# ARE_adaptadora_dsPIC-PIC32_64pin.net
KiCad netlist of a schematic drawn in EAGLE
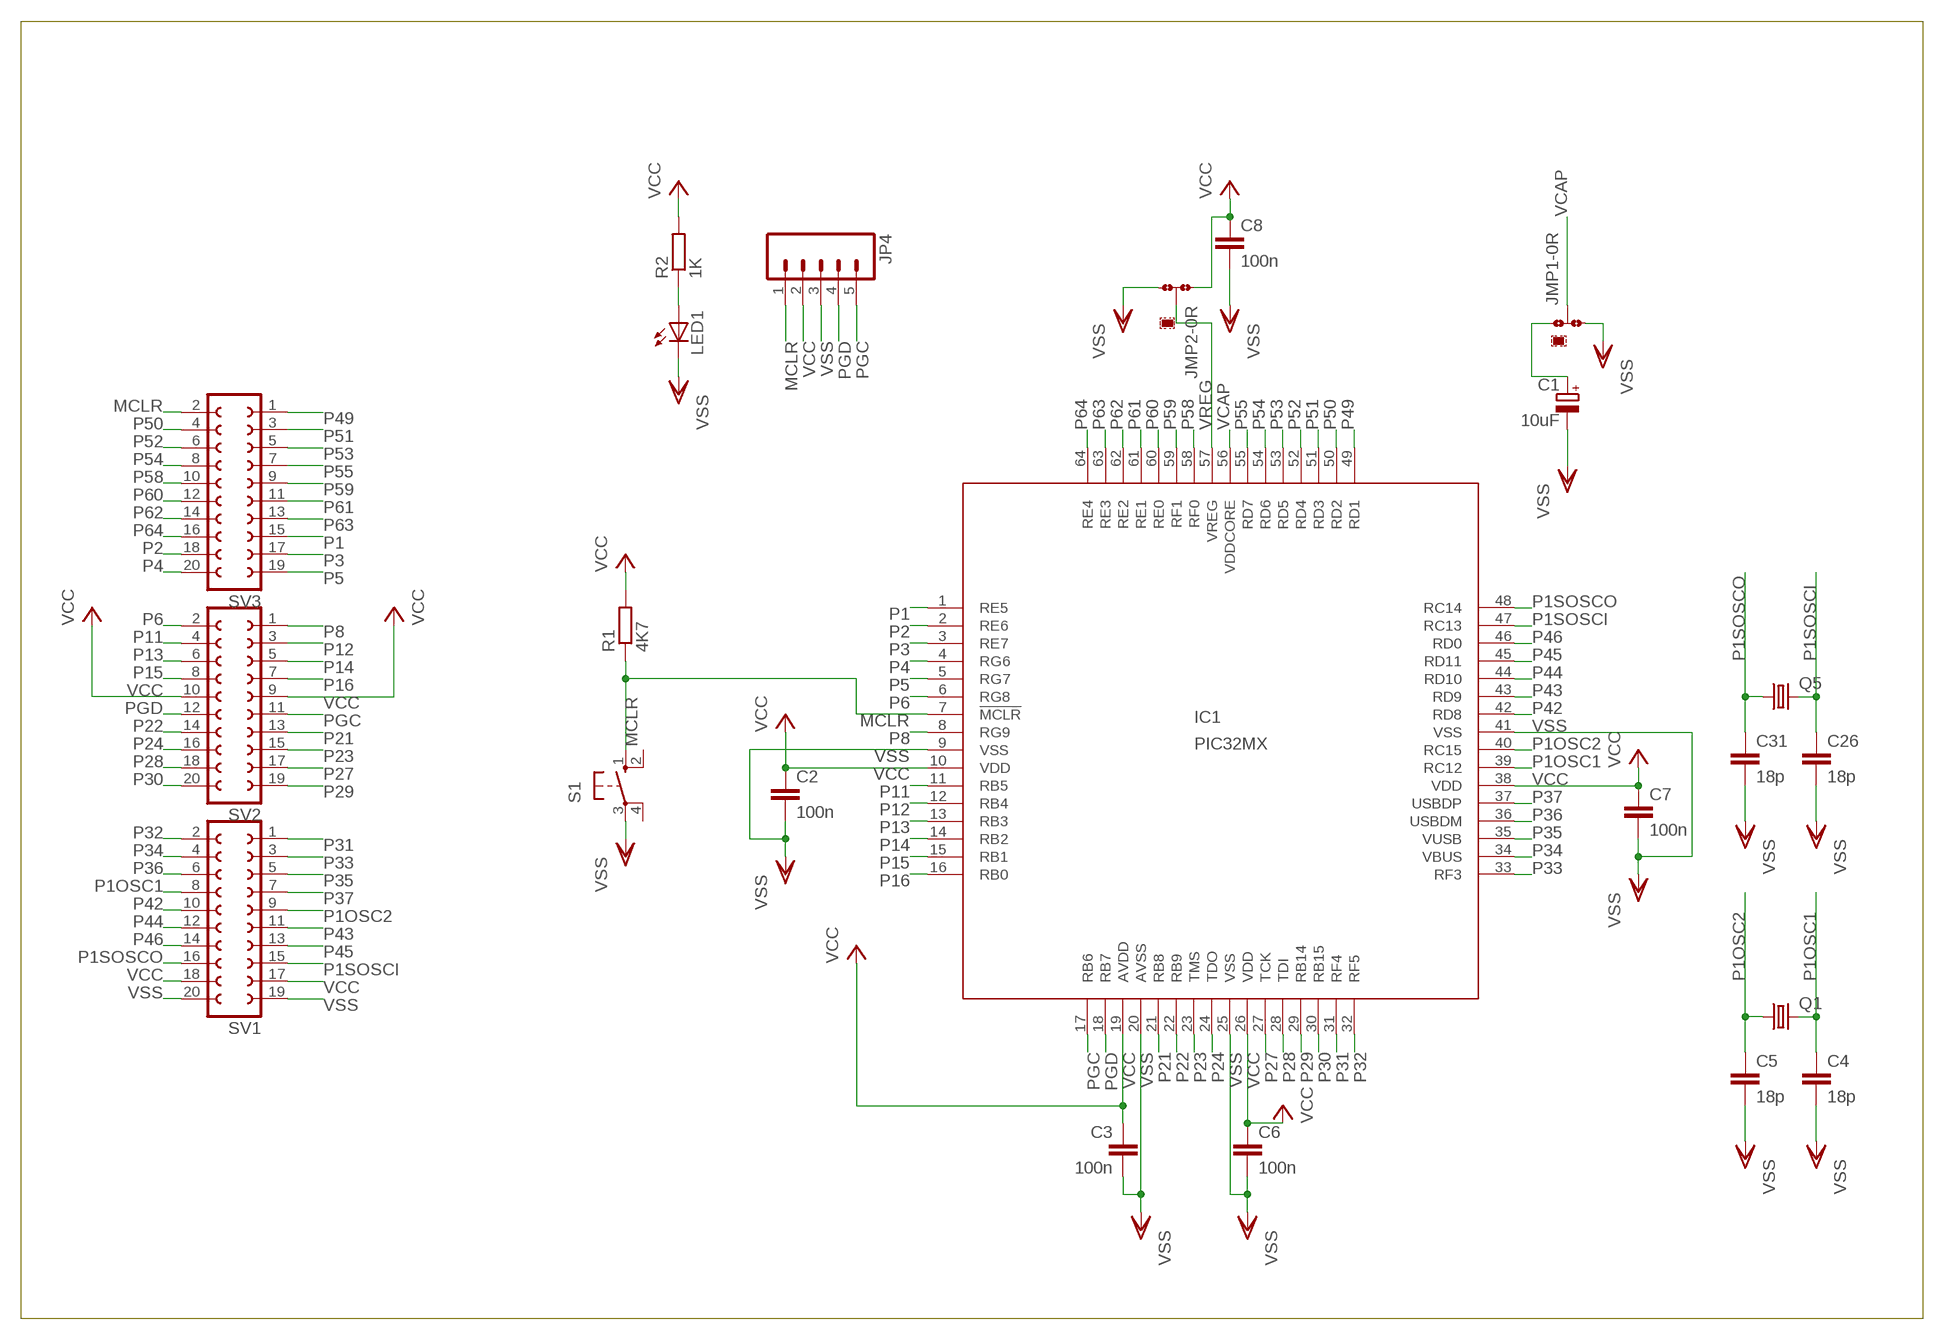
[diagram p0: schematic, sheet 1]

(export (version "E")
  (design (tool "Eeschema 10.0.6"))
  (components
    (comp (ref "C1")
      (value "10uF")
      (footprint "eagle-import:SMC_C")
      (libsource (lib "eagle-import") (part "CPOL-EUSMCC"))
    )
    (comp (ref "C2")
      (value "100n")
      (footprint "eagle-import:C0805")
      (libsource (lib "eagle-import") (part "C-EUC0805"))
    )
    (comp (ref "C3")
      (value "100n")
      (footprint "eagle-import:C0805")
      (libsource (lib "eagle-import") (part "C-EUC0805"))
    )
    (comp (ref "C4")
      (value "18p")
      (footprint "eagle-import:C0805")
      (libsource (lib "eagle-import") (part "C-EUC0805"))
    )
    (comp (ref "C5")
      (value "18p")
      (footprint "eagle-import:C0805")
      (libsource (lib "eagle-import") (part "C-EUC0805"))
    )
    (comp (ref "C6")
      (value "100n")
      (footprint "eagle-import:C0805")
      (libsource (lib "eagle-import") (part "C-EUC0805"))
    )
    (comp (ref "C7")
      (value "100n")
      (footprint "eagle-import:C0805")
      (libsource (lib "eagle-import") (part "C-EUC0805"))
    )
    (comp (ref "C8")
      (value "100n")
      (footprint "eagle-import:C0805")
      (libsource (lib "eagle-import") (part "C-EUC0805"))
    )
    (comp (ref "C26")
      (value "18p")
      (footprint "eagle-import:C0805")
      (libsource (lib "eagle-import") (part "C-EUC0805"))
    )
    (comp (ref "C31")
      (value "18p")
      (footprint "eagle-import:C0805")
      (libsource (lib "eagle-import") (part "C-EUC0805"))
    )
    (comp (ref "IC1")
      (value "PIC32MX")
      (footprint "eagle-import:TQFP64-10X10")
      (libsource (lib "eagle-import") (part "PIC32MX440F256H"))
    )
    (comp (ref "JMP1")
      (value "0R-JUMPA")
      (footprint "eagle-import:A0R-JMP")
      (libsource (lib "eagle-import") (part "0R-JUMPA"))
    )
    (comp (ref "JMP2")
      (value "0R-JUMPA")
      (footprint "eagle-import:A0R-JMP")
      (libsource (lib "eagle-import") (part "0R-JUMPA"))
    )
    (comp (ref "JP4")
      (value "M05PTH")
      (footprint "eagle-import:1X05")
      (libsource (lib "eagle-import") (part "M05PTH"))
    )
    (comp (ref "LED1")
      (value "LEDCHIPLED_0805")
      (footprint "eagle-import:CHIPLED_0805")
      (libsource (lib "eagle-import") (part "LEDCHIPLED_0805"))
    )
    (comp (ref "Q1")
      (value "CRYSTALHC18U-V")
      (footprint "eagle-import:HC18U-V")
      (libsource (lib "eagle-import") (part "CRYSTALHC18U-V"))
    )
    (comp (ref "Q5")
      (value "CRYSTALHC18U-V")
      (footprint "eagle-import:HC18U-V")
      (libsource (lib "eagle-import") (part "CRYSTALHC18U-V"))
    )
    (comp (ref "R1")
      (value "4K7")
      (footprint "eagle-import:R0805")
      (libsource (lib "eagle-import") (part "R-EU_R0805"))
    )
    (comp (ref "R2")
      (value "1K")
      (footprint "eagle-import:R0805")
      (libsource (lib "eagle-import") (part "R-EU_R0805"))
    )
    (comp (ref "S1")
      (value "10-XX")
      (footprint "eagle-import:B3F-10XX")
      (fields
        (field (name "MPN") "B3F-1000")
        (field (name "MPN_1") "B3F-1000")
        (field (name "OC_FARNELL") "176432")
        (field (name "OC_NEWARK") "36M3542")
      )
      (libsource (lib "eagle-import") (part "10-XX"))
    )
    (comp (ref "SV1")
      (value "FE10-2W")
      (footprint "eagle-import:FE10-2W")
      (libsource (lib "eagle-import") (part "FE10-2W"))
    )
    (comp (ref "SV2")
      (value "FE10-2W")
      (footprint "eagle-import:FE10-2W")
      (libsource (lib "eagle-import") (part "FE10-2W"))
    )
    (comp (ref "SV3")
      (value "FE10-2W")
      (footprint "eagle-import:FE10-2W")
      (libsource (lib "eagle-import") (part "FE10-2W"))
    )
  )
  (nets
    (net (code "1") (name "/MCLR") (class "Default")
      (node (ref "IC1") (pin "7") (pinfunction "~{MCLR}_7") (pintype "input"))
      (node (ref "JP4") (pin "1") (pinfunction "1_1") (pintype "passive"))
      (node (ref "R1") (pin "1") (pinfunction "1_1") (pintype "passive"))
      (node (ref "S1") (pin "1") (pinfunction "S_1") (pintype "passive"))
      (node (ref "SV3") (pin "2") (pinfunction "2_2") (pintype "passive"))
    )
    (net (code "2") (name "/P1") (class "Default")
      (node (ref "IC1") (pin "1") (pinfunction "RE5_1") (pintype "bidirectional"))
      (node (ref "SV3") (pin "15") (pinfunction "15_15") (pintype "passive"))
    )
    (net (code "3") (name "/P1OSC1") (class "Default")
      (node (ref "C4") (pin "1") (pinfunction "1_1") (pintype "passive"))
      (node (ref "IC1") (pin "39") (pinfunction "RC12_39") (pintype "bidirectional"))
      (node (ref "Q1") (pin "2") (pinfunction "2_2") (pintype "passive"))
      (node (ref "SV1") (pin "8") (pinfunction "8_8") (pintype "passive"))
    )
    (net (code "4") (name "/P1OSC2") (class "Default")
      (node (ref "C5") (pin "1") (pinfunction "1_1") (pintype "passive"))
      (node (ref "IC1") (pin "40") (pinfunction "RC15_40") (pintype "bidirectional"))
      (node (ref "Q1") (pin "1") (pinfunction "1_1") (pintype "passive"))
      (node (ref "SV1") (pin "9") (pinfunction "9_9") (pintype "passive"))
    )
    (net (code "5") (name "/P1SOSCI") (class "Default")
      (node (ref "C26") (pin "1") (pinfunction "1_1") (pintype "passive"))
      (node (ref "IC1") (pin "47") (pinfunction "RC13_47") (pintype "bidirectional"))
      (node (ref "Q5") (pin "2") (pinfunction "2_2") (pintype "passive"))
      (node (ref "SV1") (pin "15") (pinfunction "15_15") (pintype "passive"))
    )
    (net (code "6") (name "/P1SOSCO") (class "Default")
      (node (ref "C31") (pin "1") (pinfunction "1_1") (pintype "passive"))
      (node (ref "IC1") (pin "48") (pinfunction "RC14_48") (pintype "bidirectional"))
      (node (ref "Q5") (pin "1") (pinfunction "1_1") (pintype "passive"))
      (node (ref "SV1") (pin "16") (pinfunction "16_16") (pintype "passive"))
    )
    (net (code "7") (name "/P2") (class "Default")
      (node (ref "IC1") (pin "2") (pinfunction "RE6_2") (pintype "bidirectional"))
      (node (ref "SV3") (pin "18") (pinfunction "18_18") (pintype "passive"))
    )
    (net (code "8") (name "/P3") (class "Default")
      (node (ref "IC1") (pin "3") (pinfunction "RE7_3") (pintype "bidirectional"))
      (node (ref "SV3") (pin "17") (pinfunction "17_17") (pintype "passive"))
    )
    (net (code "9") (name "/P4") (class "Default")
      (node (ref "IC1") (pin "4") (pinfunction "RG6_4") (pintype "bidirectional"))
      (node (ref "SV3") (pin "20") (pinfunction "20_20") (pintype "passive"))
    )
    (net (code "10") (name "/P5") (class "Default")
      (node (ref "IC1") (pin "5") (pinfunction "RG7_5") (pintype "bidirectional"))
      (node (ref "SV3") (pin "19") (pinfunction "19_19") (pintype "passive"))
    )
    (net (code "11") (name "/P6") (class "Default")
      (node (ref "IC1") (pin "6") (pinfunction "RG8_6") (pintype "bidirectional"))
      (node (ref "SV2") (pin "2") (pinfunction "2_2") (pintype "passive"))
    )
    (net (code "12") (name "/P8") (class "Default")
      (node (ref "IC1") (pin "8") (pinfunction "RG9_8") (pintype "bidirectional"))
      (node (ref "SV2") (pin "1") (pinfunction "1_1") (pintype "passive"))
    )
    (net (code "13") (name "/P11") (class "Default")
      (node (ref "IC1") (pin "11") (pinfunction "RB5_11") (pintype "bidirectional"))
      (node (ref "SV2") (pin "4") (pinfunction "4_4") (pintype "passive"))
    )
    (net (code "14") (name "/P12") (class "Default")
      (node (ref "IC1") (pin "12") (pinfunction "RB4_12") (pintype "bidirectional"))
      (node (ref "SV2") (pin "3") (pinfunction "3_3") (pintype "passive"))
    )
    (net (code "15") (name "/P13") (class "Default")
      (node (ref "IC1") (pin "13") (pinfunction "RB3_13") (pintype "bidirectional"))
      (node (ref "SV2") (pin "6") (pinfunction "6_6") (pintype "passive"))
    )
    (net (code "16") (name "/P14") (class "Default")
      (node (ref "IC1") (pin "14") (pinfunction "RB2_14") (pintype "bidirectional"))
      (node (ref "SV2") (pin "5") (pinfunction "5_5") (pintype "passive"))
    )
    (net (code "17") (name "/P15") (class "Default")
      (node (ref "IC1") (pin "15") (pinfunction "RB1_15") (pintype "bidirectional"))
      (node (ref "SV2") (pin "8") (pinfunction "8_8") (pintype "passive"))
    )
    (net (code "18") (name "/P16") (class "Default")
      (node (ref "IC1") (pin "16") (pinfunction "RB0_16") (pintype "bidirectional"))
      (node (ref "SV2") (pin "7") (pinfunction "7_7") (pintype "passive"))
    )
    (net (code "19") (name "/P21") (class "Default")
      (node (ref "IC1") (pin "21") (pinfunction "RB8_21") (pintype "bidirectional"))
      (node (ref "SV2") (pin "13") (pinfunction "13_13") (pintype "passive"))
    )
    (net (code "20") (name "/P22") (class "Default")
      (node (ref "IC1") (pin "22") (pinfunction "RB9_22") (pintype "bidirectional"))
      (node (ref "SV2") (pin "14") (pinfunction "14_14") (pintype "passive"))
    )
    (net (code "21") (name "/P23") (class "Default")
      (node (ref "IC1") (pin "23") (pinfunction "TMS_23") (pintype "input"))
      (node (ref "SV2") (pin "15") (pinfunction "15_15") (pintype "passive"))
    )
    (net (code "22") (name "/P24") (class "Default")
      (node (ref "IC1") (pin "24") (pinfunction "TDO_24") (pintype "output"))
      (node (ref "SV2") (pin "16") (pinfunction "16_16") (pintype "passive"))
    )
    (net (code "23") (name "/P27") (class "Default")
      (node (ref "IC1") (pin "27") (pinfunction "TCK_27") (pintype "input"))
      (node (ref "SV2") (pin "17") (pinfunction "17_17") (pintype "passive"))
    )
    (net (code "24") (name "/P28") (class "Default")
      (node (ref "IC1") (pin "28") (pinfunction "TDI_28") (pintype "input"))
      (node (ref "SV2") (pin "18") (pinfunction "18_18") (pintype "passive"))
    )
    (net (code "25") (name "/P29") (class "Default")
      (node (ref "IC1") (pin "29") (pinfunction "RB14_29") (pintype "bidirectional"))
      (node (ref "SV2") (pin "19") (pinfunction "19_19") (pintype "passive"))
    )
    (net (code "26") (name "/P30") (class "Default")
      (node (ref "IC1") (pin "30") (pinfunction "RB15_30") (pintype "bidirectional"))
      (node (ref "SV2") (pin "20") (pinfunction "20_20") (pintype "passive"))
    )
    (net (code "27") (name "/P31") (class "Default")
      (node (ref "IC1") (pin "31") (pinfunction "RF4_31") (pintype "bidirectional"))
      (node (ref "SV1") (pin "1") (pinfunction "1_1") (pintype "passive"))
    )
    (net (code "28") (name "/P32") (class "Default")
      (node (ref "IC1") (pin "32") (pinfunction "RF5_32") (pintype "bidirectional"))
      (node (ref "SV1") (pin "2") (pinfunction "2_2") (pintype "passive"))
    )
    (net (code "29") (name "/P33") (class "Default")
      (node (ref "IC1") (pin "33") (pinfunction "RF3_33") (pintype "bidirectional"))
      (node (ref "SV1") (pin "3") (pinfunction "3_3") (pintype "passive"))
    )
    (net (code "30") (name "/P34") (class "Default")
      (node (ref "IC1") (pin "34") (pinfunction "VBUS_34") (pintype "bidirectional"))
      (node (ref "SV1") (pin "4") (pinfunction "4_4") (pintype "passive"))
    )
    (net (code "31") (name "/P35") (class "Default")
      (node (ref "IC1") (pin "35") (pinfunction "VUSB_35") (pintype "passive"))
      (node (ref "SV1") (pin "5") (pinfunction "5_5") (pintype "passive"))
    )
    (net (code "32") (name "/P36") (class "Default")
      (node (ref "IC1") (pin "36") (pinfunction "USBDM_36") (pintype "bidirectional"))
      (node (ref "SV1") (pin "6") (pinfunction "6_6") (pintype "passive"))
    )
    (net (code "33") (name "/P37") (class "Default")
      (node (ref "IC1") (pin "37") (pinfunction "USBDP_37") (pintype "bidirectional"))
      (node (ref "SV1") (pin "7") (pinfunction "7_7") (pintype "passive"))
    )
    (net (code "34") (name "/P42") (class "Default")
      (node (ref "IC1") (pin "42") (pinfunction "RD8_42") (pintype "bidirectional"))
      (node (ref "SV1") (pin "10") (pinfunction "10_10") (pintype "passive"))
    )
    (net (code "35") (name "/P43") (class "Default")
      (node (ref "IC1") (pin "43") (pinfunction "RD9_43") (pintype "bidirectional"))
      (node (ref "SV1") (pin "11") (pinfunction "11_11") (pintype "passive"))
    )
    (net (code "36") (name "/P44") (class "Default")
      (node (ref "IC1") (pin "44") (pinfunction "RD10_44") (pintype "bidirectional"))
      (node (ref "SV1") (pin "12") (pinfunction "12_12") (pintype "passive"))
    )
    (net (code "37") (name "/P45") (class "Default")
      (node (ref "IC1") (pin "45") (pinfunction "RD11_45") (pintype "bidirectional"))
      (node (ref "SV1") (pin "13") (pinfunction "13_13") (pintype "passive"))
    )
    (net (code "38") (name "/P46") (class "Default")
      (node (ref "IC1") (pin "46") (pinfunction "RD0_46") (pintype "bidirectional"))
      (node (ref "SV1") (pin "14") (pinfunction "14_14") (pintype "passive"))
    )
    (net (code "39") (name "/P49") (class "Default")
      (node (ref "IC1") (pin "49") (pinfunction "RD1_49") (pintype "bidirectional"))
      (node (ref "SV3") (pin "1") (pinfunction "1_1") (pintype "passive"))
    )
    (net (code "40") (name "/P50") (class "Default")
      (node (ref "IC1") (pin "50") (pinfunction "RD2_50") (pintype "bidirectional"))
      (node (ref "SV3") (pin "4") (pinfunction "4_4") (pintype "passive"))
    )
    (net (code "41") (name "/P51") (class "Default")
      (node (ref "IC1") (pin "51") (pinfunction "RD3_51") (pintype "bidirectional"))
      (node (ref "SV3") (pin "3") (pinfunction "3_3") (pintype "passive"))
    )
    (net (code "42") (name "/P52") (class "Default")
      (node (ref "IC1") (pin "52") (pinfunction "RD4_52") (pintype "bidirectional"))
      (node (ref "SV3") (pin "6") (pinfunction "6_6") (pintype "passive"))
    )
    (net (code "43") (name "/P53") (class "Default")
      (node (ref "IC1") (pin "53") (pinfunction "RD5_53") (pintype "bidirectional"))
      (node (ref "SV3") (pin "5") (pinfunction "5_5") (pintype "passive"))
    )
    (net (code "44") (name "/P54") (class "Default")
      (node (ref "IC1") (pin "54") (pinfunction "RD6_54") (pintype "bidirectional"))
      (node (ref "SV3") (pin "8") (pinfunction "8_8") (pintype "passive"))
    )
    (net (code "45") (name "/P55") (class "Default")
      (node (ref "IC1") (pin "55") (pinfunction "RD7_55") (pintype "bidirectional"))
      (node (ref "SV3") (pin "7") (pinfunction "7_7") (pintype "passive"))
    )
    (net (code "46") (name "/P58") (class "Default")
      (node (ref "IC1") (pin "58") (pinfunction "RF0_58") (pintype "bidirectional"))
      (node (ref "SV3") (pin "10") (pinfunction "10_10") (pintype "passive"))
    )
    (net (code "47") (name "/P59") (class "Default")
      (node (ref "IC1") (pin "59") (pinfunction "RF1_59") (pintype "bidirectional"))
      (node (ref "SV3") (pin "9") (pinfunction "9_9") (pintype "passive"))
    )
    (net (code "48") (name "/P60") (class "Default")
      (node (ref "IC1") (pin "60") (pinfunction "RE0_60") (pintype "bidirectional"))
      (node (ref "SV3") (pin "12") (pinfunction "12_12") (pintype "passive"))
    )
    (net (code "49") (name "/P61") (class "Default")
      (node (ref "IC1") (pin "61") (pinfunction "RE1_61") (pintype "bidirectional"))
      (node (ref "SV3") (pin "11") (pinfunction "11_11") (pintype "passive"))
    )
    (net (code "50") (name "/P62") (class "Default")
      (node (ref "IC1") (pin "62") (pinfunction "RE2_62") (pintype "bidirectional"))
      (node (ref "SV3") (pin "14") (pinfunction "14_14") (pintype "passive"))
    )
    (net (code "51") (name "/P63") (class "Default")
      (node (ref "IC1") (pin "63") (pinfunction "RE3_63") (pintype "bidirectional"))
      (node (ref "SV3") (pin "13") (pinfunction "13_13") (pintype "passive"))
    )
    (net (code "52") (name "/P64") (class "Default")
      (node (ref "IC1") (pin "64") (pinfunction "RE4_64") (pintype "bidirectional"))
      (node (ref "SV3") (pin "16") (pinfunction "16_16") (pintype "passive"))
    )
    (net (code "53") (name "/PGC") (class "Default")
      (node (ref "IC1") (pin "17") (pinfunction "RB6_17") (pintype "bidirectional"))
      (node (ref "JP4") (pin "5") (pinfunction "5_5") (pintype "passive"))
      (node (ref "SV2") (pin "11") (pinfunction "11_11") (pintype "passive"))
    )
    (net (code "54") (name "/PGD") (class "Default")
      (node (ref "IC1") (pin "18") (pinfunction "RB7_18") (pintype "bidirectional"))
      (node (ref "JP4") (pin "4") (pinfunction "4_4") (pintype "passive"))
      (node (ref "SV2") (pin "12") (pinfunction "12_12") (pintype "passive"))
    )
    (net (code "55") (name "/VCAP") (class "Default")
      (node (ref "IC1") (pin "56") (pinfunction "VDDCORE_56") (pintype "power_in"))
      (node (ref "JMP1") (pin "2") (pinfunction "2_2") (pintype "passive"))
    )
    (net (code "56") (name "/VREG") (class "Default")
      (node (ref "IC1") (pin "57") (pinfunction "VREG_57") (pintype "passive"))
      (node (ref "JMP2") (pin "2") (pinfunction "2_2") (pintype "passive"))
    )
    (net (code "57") (name "Net-(C1-Pad+)") (class "Default")
      (node (ref "C1") (pin "+") (pinfunction "+_+") (pintype "passive"))
      (node (ref "JMP1") (pin "1") (pinfunction "1_1") (pintype "passive"))
    )
    (net (code "58") (name "Net-(LED1-PadA)") (class "Default")
      (node (ref "LED1") (pin "A") (pinfunction "A_A") (pintype "passive"))
      (node (ref "R2") (pin "1") (pinfunction "1_1") (pintype "passive"))
    )
    (net (code "59") (name "VCC") (class "Default")
      (node (ref "C2") (pin "1") (pinfunction "1_1") (pintype "passive"))
      (node (ref "C3") (pin "1") (pinfunction "1_1") (pintype "passive"))
      (node (ref "C6") (pin "1") (pinfunction "1_1") (pintype "passive"))
      (node (ref "C7") (pin "1") (pinfunction "1_1") (pintype "passive"))
      (node (ref "C8") (pin "1") (pinfunction "1_1") (pintype "passive"))
      (node (ref "IC1") (pin "10") (pinfunction "VDD_10") (pintype "power_in"))
      (node (ref "IC1") (pin "19") (pinfunction "AVDD_19") (pintype "power_in"))
      (node (ref "IC1") (pin "26") (pinfunction "VDD_26") (pintype "power_in"))
      (node (ref "IC1") (pin "38") (pinfunction "VDD_38") (pintype "power_in"))
      (node (ref "JMP2") (pin "1") (pinfunction "1_1") (pintype "passive"))
      (node (ref "JP4") (pin "2") (pinfunction "2_2") (pintype "passive"))
      (node (ref "R1") (pin "2") (pinfunction "2_2") (pintype "passive"))
      (node (ref "R2") (pin "2") (pinfunction "2_2") (pintype "passive"))
      (node (ref "SV1") (pin "17") (pinfunction "17_17") (pintype "passive"))
      (node (ref "SV1") (pin "18") (pinfunction "18_18") (pintype "passive"))
      (node (ref "SV2") (pin "10") (pinfunction "10_10") (pintype "passive"))
      (node (ref "SV2") (pin "9") (pinfunction "9_9") (pintype "passive"))
    )
    (net (code "60") (name "VSS") (class "Default")
      (node (ref "C1") (pin "-") (pinfunction "-_-") (pintype "passive"))
      (node (ref "C2") (pin "2") (pinfunction "2_2") (pintype "passive"))
      (node (ref "C26") (pin "2") (pinfunction "2_2") (pintype "passive"))
      (node (ref "C3") (pin "2") (pinfunction "2_2") (pintype "passive"))
      (node (ref "C31") (pin "2") (pinfunction "2_2") (pintype "passive"))
      (node (ref "C4") (pin "2") (pinfunction "2_2") (pintype "passive"))
      (node (ref "C5") (pin "2") (pinfunction "2_2") (pintype "passive"))
      (node (ref "C6") (pin "2") (pinfunction "2_2") (pintype "passive"))
      (node (ref "C7") (pin "2") (pinfunction "2_2") (pintype "passive"))
      (node (ref "C8") (pin "2") (pinfunction "2_2") (pintype "passive"))
      (node (ref "IC1") (pin "20") (pinfunction "AVSS_20") (pintype "power_in"))
      (node (ref "IC1") (pin "25") (pinfunction "VSS_25") (pintype "power_in"))
      (node (ref "IC1") (pin "41") (pinfunction "VSS_41") (pintype "power_in"))
      (node (ref "IC1") (pin "9") (pinfunction "VSS_9") (pintype "power_in"))
      (node (ref "JMP1") (pin "3") (pinfunction "3_3") (pintype "passive"))
      (node (ref "JMP2") (pin "3") (pinfunction "3_3") (pintype "passive"))
      (node (ref "JP4") (pin "3") (pinfunction "3_3") (pintype "passive"))
      (node (ref "LED1") (pin "C") (pinfunction "C_C") (pintype "passive"))
      (node (ref "S1") (pin "3") (pinfunction "P_3") (pintype "passive"))
      (node (ref "SV1") (pin "19") (pinfunction "19_19") (pintype "passive"))
      (node (ref "SV1") (pin "20") (pinfunction "20_20") (pintype "passive"))
    )
    (net (code "61") (name "unconnected-(S1-P1-Pad4)") (class "Default")
      (node (ref "S1") (pin "4") (pinfunction "P1_4") (pintype "passive"))
    )
    (net (code "62") (name "unconnected-(S1-S1-Pad2)") (class "Default")
      (node (ref "S1") (pin "2") (pinfunction "S1_2") (pintype "passive"))
    )
  )
)
